# Sheet1.net
KiCad netlist of a schematic drawn in Altium Designer
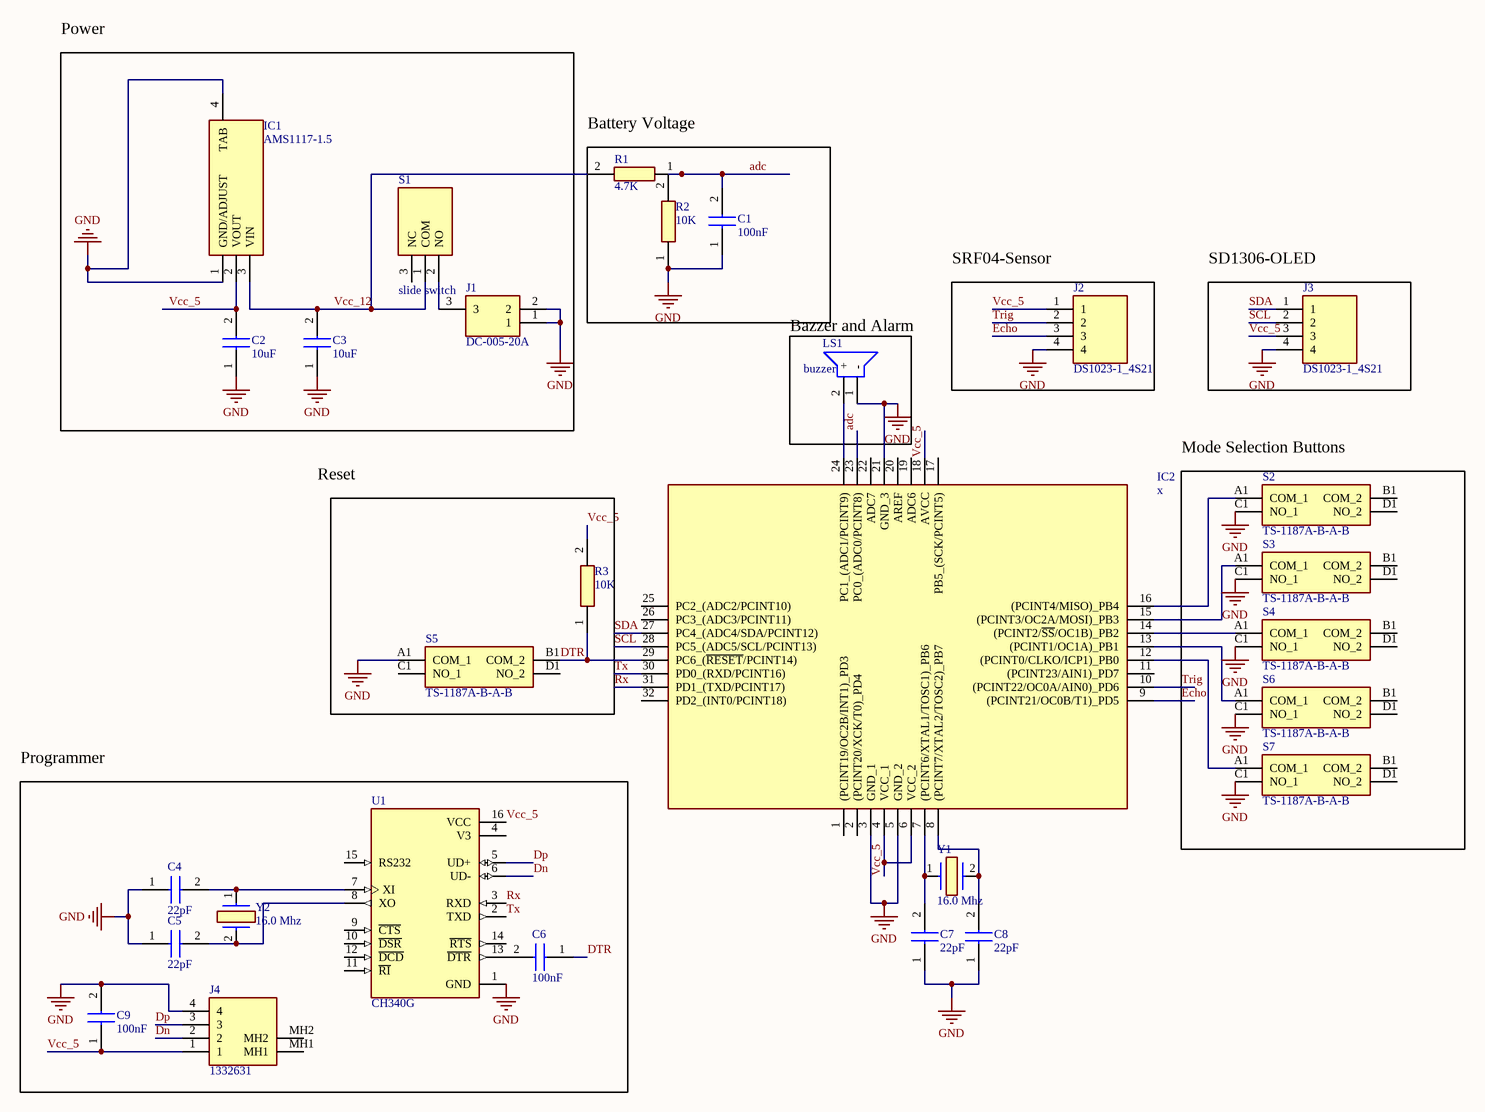
[diagram p0: Sheet1.SchDoc]

(export (version "E")
  (design (tool "Eeschema 10.0.6"))
  (components
    (comp (ref "C1")
      (value "100nF")
      (footprint "SamacSys:CAPC2012X130N")
      (description "Capacitor")
      (fields
        (field (name "MANUFACTURER_PART_NUMBER") "0805Y1000104KET")
        (field (name "MOUSER PART NUMBER") "843-0805Y1000104KET")
      )
      (libsource (lib "*") (part "0805Y1000104KET"))
    )
    (comp (ref "C2")
      (value "10uF")
      (footprint "SamacSys:CAPC2012X130N")
      (description "Capacitor")
      (fields
        (field (name "MANUFACTURER_PART_NUMBER") "0805Y1000104KET")
        (field (name "MOUSER PART NUMBER") "843-0805Y1000104KET")
      )
      (libsource (lib "*") (part "0805Y1000104KET"))
    )
    (comp (ref "C3")
      (value "10uF")
      (footprint "SamacSys:CAPC2012X130N")
      (description "Capacitor")
      (fields
        (field (name "MANUFACTURER_PART_NUMBER") "0805Y1000104KET")
        (field (name "MOUSER PART NUMBER") "843-0805Y1000104KET")
      )
      (libsource (lib "*") (part "0805Y1000104KET"))
    )
    (comp (ref "C4")
      (value "22pF")
      (footprint "SamacSys:CAPC2012X130N")
      (description "Capacitor")
      (fields (field (name "MANUFACTURER_PART_NUMBER") "0805J050 0223MXE01"))
      (libsource (lib "*") (part "0805J050_0223MXE01"))
    )
    (comp (ref "C5")
      (value "22pF")
      (footprint "SamacSys:CAPC2012X130N")
      (description "Capacitor")
      (fields (field (name "MANUFACTURER_PART_NUMBER") "0805J050 0223MXE01"))
      (libsource (lib "*") (part "0805J050_0223MXE01"))
    )
    (comp (ref "C6")
      (value "100nF")
      (footprint "SamacSys:CAPC2012X130N")
      (description "Capacitor")
      (fields (field (name "MANUFACTURER_PART_NUMBER") "0805J050 0223MXE01"))
      (libsource (lib "*") (part "0805J050_0223MXE01"))
    )
    (comp (ref "C7")
      (value "22pF")
      (footprint "SamacSys:CAPC2012X130N")
      (description "Capacitor")
      (fields (field (name "MANUFACTURER_PART_NUMBER") "0805J050 0223MXE01"))
      (libsource (lib "*") (part "0805J050_0223MXE01"))
    )
    (comp (ref "C8")
      (value "22pF")
      (footprint "SamacSys:CAPC2012X130N")
      (description "Capacitor")
      (fields (field (name "MANUFACTURER_PART_NUMBER") "0805J050 0223MXE01"))
      (libsource (lib "*") (part "0805J050_0223MXE01"))
    )
    (comp (ref "C9")
      (value "100nF")
      (footprint "SamacSys:CAPC2012X130N")
      (description "Capacitor")
      (fields (field (name "MANUFACTURER_PART_NUMBER") "0805J050 0223MXE01"))
      (libsource (lib "*") (part "0805J050_0223MXE01"))
    )
    (comp (ref "IC1")
      (value "AMS1117-1.5")
      (footprint "SamacSys:SOT229P700X180-4N")
      (description "Integrated Circuit")
      (libsource (lib "*") (part "AMS1117-1.5"))
    )
    (comp (ref "IC2")
      (value "x")
      (footprint "SamacSys:QFP80P900X900X120-32N")
      (description "Integrated Circuit")
      (fields
        (field (name "MANUFACTURER_PART_NUMBER") "ATMEGA328-AU")
        (field (name "MOUSER PART NUMBER") "556-ATMEGA328-AU")
      )
      (libsource (lib "*") (part "ATMEGA328-AU"))
    )
    (comp (ref "J1")
      (value "DC-005-20A")
      (footprint "SamacSys:DC00520A")
      (description "Connector")
      (libsource (lib "*") (part "DC-005-20A"))
    )
    (comp (ref "J2")
      (value "DS1023-1_4S21")
      (footprint "SamacSys:RHDR4W60P0X254_1X4_1016X250X840P")
      (description "Connector")
      (fields (field (name "MANUFACTURER_PART_NUMBER") "DS1023-1*4S21"))
      (libsource (lib "*") (part "DS1023-1_4S21"))
    )
    (comp (ref "J3")
      (value "DS1023-1_4S21")
      (footprint "SamacSys:RHDR4W60P0X254_1X4_1016X250X840P")
      (description "Connector")
      (fields (field (name "MANUFACTURER_PART_NUMBER") "DS1023-1*4S21"))
      (libsource (lib "*") (part "DS1023-1_4S21"))
    )
    (comp (ref "J4")
      (value "1332631")
      (footprint "SamacSys:1332631")
      (description "Connector")
      (libsource (lib "*") (part "1332631"))
    )
    (comp (ref "LS1")
      (value "buzzer")
      (footprint "SamacSys:CT1205SMTTR")
      (description "Loudspeaker or Buzzer")
      (fields
        (field (name "MANUFACTURER_PART_NUMBER") "CT-1205-SMT-TR")
        (field (name "MOUSER PART NUMBER") "490-CT-1205-SMT-TR")
      )
      (libsource (lib "*") (part "CT-1205-SMT-TR"))
    )
    (comp (ref "R1")
      (value "4.7K")
      (footprint "SamacSys:RESC2012X60N")
      (description "Resistor")
      (fields
        (field (name "MANUFACTURER_PART_NUMBER") "CRCW080510K0FKEAHP")
        (field (name "MOUSER PART NUMBER") "71-CRCW080510K0FKEAH")
      )
      (libsource (lib "") (part "CRCW080510K0FKEAHP_1"))
    )
    (comp (ref "R2")
      (value "10K")
      (footprint "SamacSys:RESC2012X60N")
      (description "Resistor")
      (fields
        (field (name "MANUFACTURER_PART_NUMBER") "CRCW080510K0FKEAHP")
        (field (name "MOUSER PART NUMBER") "71-CRCW080510K0FKEAH")
      )
      (libsource (lib "*") (part "CRCW080510K0FKEAHP"))
    )
    (comp (ref "R3")
      (value "10K")
      (footprint "SamacSys:RESC2012X60N")
      (description "Resistor")
      (fields
        (field (name "MANUFACTURER_PART_NUMBER") "CRCW080510K0FKEAHP")
        (field (name "MOUSER PART NUMBER") "71-CRCW080510K0FKEAH")
      )
      (libsource (lib "*") (part "CRCW080510K0FKEAHP"))
    )
    (comp (ref "S1")
      (value "slide switch")
      (footprint "SamacSys:090329001")
      (description "Switch")
      (fields
        (field (name "MANUFACTURER_PART_NUMBER") "09.03290.01")
        (field (name "MOUSER PART NUMBER") "123-09.03290.01")
      )
      (libsource (lib "*") (part "09.03290.01"))
    )
    (comp (ref "S2")
      (value "TS-1187A-B-A-B")
      (footprint "SamacSys:TS1187ABAB")
      (description "Switch")
      (libsource (lib "*") (part "TS-1187A-B-A-B"))
    )
    (comp (ref "S3")
      (value "TS-1187A-B-A-B")
      (footprint "SamacSys:TS1187ABAB")
      (description "Switch")
      (libsource (lib "*") (part "TS-1187A-B-A-B"))
    )
    (comp (ref "S4")
      (value "TS-1187A-B-A-B")
      (footprint "SamacSys:TS1187ABAB")
      (description "Switch")
      (libsource (lib "*") (part "TS-1187A-B-A-B"))
    )
    (comp (ref "S5")
      (value "TS-1187A-B-A-B")
      (footprint "SamacSys:TS1187ABAB")
      (description "Switch")
      (libsource (lib "*") (part "TS-1187A-B-A-B"))
    )
    (comp (ref "S6")
      (value "TS-1187A-B-A-B")
      (footprint "SamacSys:TS1187ABAB")
      (description "Switch")
      (libsource (lib "*") (part "TS-1187A-B-A-B"))
    )
    (comp (ref "S7")
      (value "TS-1187A-B-A-B")
      (footprint "SamacSys:TS1187ABAB")
      (description "Switch")
      (libsource (lib "*") (part "TS-1187A-B-A-B"))
    )
    (comp (ref "U1")
      (value "CH340G")
      (footprint "SOIC127P600X180-16N")
      (description "USB Interface Integrated Circuit")
      (fields (field (name "MP") "Ch340G") (field (name "MF") "WCH"))
      (libsource (lib "CH340G") (part "CH340G"))
    )
    (comp (ref "Y1")
      (value "16.0 Mhz")
      (footprint "SamacSys:16000MHz49USMX3050408518pFATF")
      (description "Crystal or Oscillator")
      (fields (field (name "MANUFACTURER_PART_NUMBER") "16.000MHz 49USMX/30/50/-40+85/18pF/ATF"))
      (libsource (lib "*") (part "16.000MHz_49USMX_30_50_-40+85_18pF_ATF"))
    )
    (comp (ref "Y2")
      (value "16.0 Mhz")
      (footprint "SamacSys:16000MHz49USMX3050408518pFATF")
      (description "Crystal or Oscillator")
      (fields (field (name "MANUFACTURER_PART_NUMBER") "16.000MHz 49USMX/30/50/-40+85/18pF/ATF"))
      (libsource (lib "") (part "16.000MHz_49USMX_30_50_-40+85_18pF_ATF_1"))
    )
  )
  (nets
    (net (code "1") (name "/DTR") (class "Default")
      (node (ref "C6") (pin "1") (pinfunction "1_1") (pintype "passive"))
      (node (ref "IC2") (pin "29") (pinfunction "PC6_(~{RESET}/PCINT14)_29") (pintype "passive"))
      (node (ref "R3") (pin "1") (pinfunction "1_1") (pintype "passive"))
      (node (ref "S5") (pin "B1") (pinfunction "COM_2_B1") (pintype "passive"))
    )
    (net (code "2") (name "/Dn") (class "Default")
      (node (ref "J4") (pin "2") (pinfunction "2_2") (pintype "passive"))
      (node (ref "U1") (pin "6") (pinfunction "UD-_6") (pintype "bidirectional"))
    )
    (net (code "3") (name "/Dp") (class "Default")
      (node (ref "J4") (pin "3") (pinfunction "3_3") (pintype "passive"))
      (node (ref "U1") (pin "5") (pinfunction "UD+_5") (pintype "bidirectional"))
    )
    (net (code "4") (name "/Echo") (class "Default")
      (node (ref "IC2") (pin "9") (pinfunction "(PCINT21/OC0B/T1)_PD5_9") (pintype "passive"))
      (node (ref "J2") (pin "3") (pinfunction "3_3") (pintype "passive"))
    )
    (net (code "5") (name "/Rx") (class "Default")
      (node (ref "IC2") (pin "31") (pinfunction "PD1_(TXD/PCINT17)_31") (pintype "passive"))
      (node (ref "U1") (pin "3") (pinfunction "RXD_3") (pintype "input"))
    )
    (net (code "6") (name "/SCL") (class "Default")
      (node (ref "IC2") (pin "28") (pinfunction "PC5_(ADC5/SCL/PCINT13)_28") (pintype "passive"))
      (node (ref "J3") (pin "2") (pinfunction "2_2") (pintype "passive"))
    )
    (net (code "7") (name "/SDA") (class "Default")
      (node (ref "IC2") (pin "27") (pinfunction "PC4_(ADC4/SDA/PCINT12)_27") (pintype "passive"))
      (node (ref "J3") (pin "1") (pinfunction "1_1") (pintype "passive"))
    )
    (net (code "8") (name "/Trig") (class "Default")
      (node (ref "IC2") (pin "10") (pinfunction "(PCINT22/OC0A/AIN0)_PD6_10") (pintype "passive"))
      (node (ref "J2") (pin "2") (pinfunction "2_2") (pintype "passive"))
    )
    (net (code "9") (name "/Tx") (class "Default")
      (node (ref "IC2") (pin "30") (pinfunction "PD0_(RXD/PCINT16)_30") (pintype "passive"))
      (node (ref "U1") (pin "2") (pinfunction "TXD_2") (pintype "output"))
    )
    (net (code "10") (name "/Vcc_5") (class "Default")
      (node (ref "C2") (pin "2") (pinfunction "2_2") (pintype "passive"))
      (node (ref "C9") (pin "1") (pinfunction "1_1") (pintype "passive"))
      (node (ref "IC1") (pin "2") (pinfunction "VOUT_2") (pintype "passive"))
      (node (ref "IC2") (pin "18") (pinfunction "AVCC_18") (pintype "passive"))
      (node (ref "IC2") (pin "4") (pinfunction "VCC_1_4") (pintype "passive"))
      (node (ref "IC2") (pin "6") (pinfunction "VCC_2_6") (pintype "passive"))
      (node (ref "J2") (pin "1") (pinfunction "1_1") (pintype "passive"))
      (node (ref "J3") (pin "3") (pinfunction "3_3") (pintype "passive"))
      (node (ref "J4") (pin "1") (pinfunction "1_1") (pintype "passive"))
      (node (ref "R3") (pin "2") (pinfunction "2_2") (pintype "passive"))
      (node (ref "U1") (pin "16") (pinfunction "VCC_16") (pintype "power_in"))
    )
    (net (code "11") (name "/Vcc_12") (class "Default")
      (node (ref "C3") (pin "2") (pinfunction "2_2") (pintype "passive"))
      (node (ref "IC1") (pin "3") (pinfunction "VIN_3") (pintype "passive"))
      (node (ref "R1") (pin "2") (pinfunction "2_2") (pintype "passive"))
      (node (ref "S1") (pin "1") (pinfunction "COM_1") (pintype "passive"))
    )
    (net (code "12") (name "/adc") (class "Default")
      (node (ref "C1") (pin "2") (pinfunction "2_2") (pintype "passive"))
      (node (ref "IC2") (pin "23") (pinfunction "PC0_(ADC0/PCINT8)_23") (pintype "passive"))
      (node (ref "R1") (pin "1") (pinfunction "1_1") (pintype "passive"))
      (node (ref "R2") (pin "2") (pinfunction "2_2") (pintype "passive"))
    )
    (net (code "13") (name "GND") (class "Default")
      (node (ref "C1") (pin "1") (pinfunction "1_1") (pintype "passive"))
      (node (ref "C2") (pin "1") (pinfunction "1_1") (pintype "passive"))
      (node (ref "C3") (pin "1") (pinfunction "1_1") (pintype "passive"))
      (node (ref "C4") (pin "1") (pinfunction "1_1") (pintype "passive"))
      (node (ref "C5") (pin "1") (pinfunction "1_1") (pintype "passive"))
      (node (ref "C7") (pin "1") (pinfunction "1_1") (pintype "passive"))
      (node (ref "C8") (pin "1") (pinfunction "1_1") (pintype "passive"))
      (node (ref "C9") (pin "2") (pinfunction "2_2") (pintype "passive"))
      (node (ref "IC1") (pin "1") (pinfunction "GND/ADJUST_1") (pintype "passive"))
      (node (ref "IC1") (pin "4") (pinfunction "TAB_4") (pintype "passive"))
      (node (ref "IC2") (pin "21") (pinfunction "GND_3_21") (pintype "passive"))
      (node (ref "IC2") (pin "3") (pinfunction "GND_1_3") (pintype "passive"))
      (node (ref "IC2") (pin "5") (pinfunction "GND_2_5") (pintype "passive"))
      (node (ref "J1") (pin "1") (pinfunction "1_1") (pintype "passive"))
      (node (ref "J1") (pin "2") (pinfunction "2_2") (pintype "passive"))
      (node (ref "J2") (pin "4") (pinfunction "4_4") (pintype "passive"))
      (node (ref "J3") (pin "4") (pinfunction "4_4") (pintype "passive"))
      (node (ref "J4") (pin "4") (pinfunction "4_4") (pintype "passive"))
      (node (ref "LS1") (pin "1") (pinfunction "-_1") (pintype "passive"))
      (node (ref "R2") (pin "1") (pinfunction "1_1") (pintype "passive"))
      (node (ref "S2") (pin "C1") (pinfunction "NO_1_C1") (pintype "passive"))
      (node (ref "S3") (pin "C1") (pinfunction "NO_1_C1") (pintype "passive"))
      (node (ref "S4") (pin "C1") (pinfunction "NO_1_C1") (pintype "passive"))
      (node (ref "S5") (pin "A1") (pinfunction "COM_1_A1") (pintype "passive"))
      (node (ref "S6") (pin "C1") (pinfunction "NO_1_C1") (pintype "passive"))
      (node (ref "S7") (pin "C1") (pinfunction "NO_1_C1") (pintype "passive"))
      (node (ref "U1") (pin "1") (pinfunction "GND_1") (pintype "power_in"))
    )
    (net (code "14") (name "Net-(IC2-(PCINT0{slash}CLKO{slash}ICP1)_PB0)") (class "Default")
      (node (ref "IC2") (pin "12") (pinfunction "(PCINT0/CLKO/ICP1)_PB0_12") (pintype "passive"))
      (node (ref "S7") (pin "A1") (pinfunction "COM_1_A1") (pintype "passive"))
    )
    (net (code "15") (name "Net-(IC2-(PCINT1{slash}OC1A)_PB1)") (class "Default")
      (node (ref "IC2") (pin "13") (pinfunction "(PCINT1/OC1A)_PB1_13") (pintype "passive"))
      (node (ref "S6") (pin "A1") (pinfunction "COM_1_A1") (pintype "passive"))
    )
    (net (code "16") (name "Net-(IC2-(PCINT2{slash}~{SS}{slash}OC1B)_PB2)") (class "Default")
      (node (ref "IC2") (pin "14") (pinfunction "(PCINT2/~{SS}/OC1B)_PB2_14") (pintype "passive"))
      (node (ref "S4") (pin "A1") (pinfunction "COM_1_A1") (pintype "passive"))
    )
    (net (code "17") (name "Net-(IC2-(PCINT3{slash}OC2A{slash}MOSI)_PB3)") (class "Default")
      (node (ref "IC2") (pin "15") (pinfunction "(PCINT3/OC2A/MOSI)_PB3_15") (pintype "passive"))
      (node (ref "S3") (pin "A1") (pinfunction "COM_1_A1") (pintype "passive"))
    )
    (net (code "18") (name "Net-(IC2-(PCINT4{slash}MISO)_PB4)") (class "Default")
      (node (ref "IC2") (pin "16") (pinfunction "(PCINT4/MISO)_PB4_16") (pintype "passive"))
      (node (ref "S2") (pin "A1") (pinfunction "COM_1_A1") (pintype "passive"))
    )
    (net (code "19") (name "Net-(IC2-(PCINT6{slash}XTAL1{slash}TOSC1)_PB6)") (class "Default")
      (node (ref "C7") (pin "2") (pinfunction "2_2") (pintype "passive"))
      (node (ref "IC2") (pin "7") (pinfunction "(PCINT6/XTAL1/TOSC1)_PB6_7") (pintype "passive"))
      (node (ref "Y1") (pin "1") (pinfunction "1_1") (pintype "passive"))
    )
    (net (code "20") (name "Net-(IC2-(PCINT7{slash}XTAL2{slash}TOSC2)_PB7)") (class "Default")
      (node (ref "C8") (pin "2") (pinfunction "2_2") (pintype "passive"))
      (node (ref "IC2") (pin "8") (pinfunction "(PCINT7/XTAL2/TOSC2)_PB7_8") (pintype "passive"))
      (node (ref "Y1") (pin "2") (pinfunction "2_2") (pintype "passive"))
    )
    (net (code "21") (name "Net-(IC2-PC1_(ADC1{slash}PCINT9))") (class "Default")
      (node (ref "IC2") (pin "24") (pinfunction "PC1_(ADC1/PCINT9)_24") (pintype "passive"))
      (node (ref "LS1") (pin "2") (pinfunction "+_2") (pintype "passive"))
    )
    (net (code "22") (name "Net-(S1-NO)") (class "Default")
      (node (ref "J1") (pin "3") (pinfunction "3_3") (pintype "passive"))
      (node (ref "S1") (pin "2") (pinfunction "NO_2") (pintype "passive"))
    )
    (net (code "23") (name "Net-(U1-XI)") (class "Default")
      (node (ref "C4") (pin "2") (pinfunction "2_2") (pintype "passive"))
      (node (ref "U1") (pin "7") (pinfunction "XI_7") (pintype "input"))
      (node (ref "Y2") (pin "1") (pinfunction "1_1") (pintype "passive"))
    )
    (net (code "24") (name "Net-(U1-XO)") (class "Default")
      (node (ref "C5") (pin "2") (pinfunction "2_2") (pintype "passive"))
      (node (ref "U1") (pin "8") (pinfunction "XO_8") (pintype "output"))
      (node (ref "Y2") (pin "2") (pinfunction "2_2") (pintype "passive"))
    )
    (net (code "25") (name "Net-(U1-~{DTR})") (class "Default")
      (node (ref "C6") (pin "2") (pinfunction "2_2") (pintype "passive"))
      (node (ref "U1") (pin "13") (pinfunction "~{DTR}_13") (pintype "output"))
    )
    (net (code "26") (name "unconnected-(IC2-(PCINT19{slash}OC2B{slash}INT1)_PD3-Pad1)") (class "Default")
      (node (ref "IC2") (pin "1") (pinfunction "(PCINT19/OC2B/INT1)_PD3_1") (pintype "passive"))
    )
    (net (code "27") (name "unconnected-(IC2-(PCINT20{slash}XCK{slash}T0)_PD4-Pad2)") (class "Default")
      (node (ref "IC2") (pin "2") (pinfunction "(PCINT20/XCK/T0)_PD4_2") (pintype "passive"))
    )
    (net (code "28") (name "unconnected-(IC2-(PCINT23{slash}AIN1)_PD7-Pad11)") (class "Default")
      (node (ref "IC2") (pin "11") (pinfunction "(PCINT23/AIN1)_PD7_11") (pintype "passive"))
    )
    (net (code "29") (name "unconnected-(IC2-ADC6-Pad19)") (class "Default")
      (node (ref "IC2") (pin "19") (pinfunction "ADC6_19") (pintype "passive"))
    )
    (net (code "30") (name "unconnected-(IC2-ADC7-Pad22)") (class "Default")
      (node (ref "IC2") (pin "22") (pinfunction "ADC7_22") (pintype "passive"))
    )
    (net (code "31") (name "unconnected-(IC2-AREF-Pad20)") (class "Default")
      (node (ref "IC2") (pin "20") (pinfunction "AREF_20") (pintype "passive"))
    )
    (net (code "32") (name "unconnected-(IC2-PB5_(SCK{slash}PCINT5)-Pad17)") (class "Default")
      (node (ref "IC2") (pin "17") (pinfunction "PB5_(SCK/PCINT5)_17") (pintype "passive"))
    )
    (net (code "33") (name "unconnected-(IC2-PC2_(ADC2{slash}PCINT10)-Pad25)") (class "Default")
      (node (ref "IC2") (pin "25") (pinfunction "PC2_(ADC2/PCINT10)_25") (pintype "passive"))
    )
    (net (code "34") (name "unconnected-(IC2-PC3_(ADC3{slash}PCINT11)-Pad26)") (class "Default")
      (node (ref "IC2") (pin "26") (pinfunction "PC3_(ADC3/PCINT11)_26") (pintype "passive"))
    )
    (net (code "35") (name "unconnected-(IC2-PD2_(INT0{slash}PCINT18)-Pad32)") (class "Default")
      (node (ref "IC2") (pin "32") (pinfunction "PD2_(INT0/PCINT18)_32") (pintype "passive"))
    )
    (net (code "36") (name "unconnected-(J4-PadMH1)") (class "Default")
      (node (ref "J4") (pin "MH1") (pinfunction "MH1_MH1") (pintype "passive"))
    )
    (net (code "37") (name "unconnected-(J4-PadMH2)") (class "Default")
      (node (ref "J4") (pin "MH2") (pinfunction "MH2_MH2") (pintype "passive"))
    )
    (net (code "38") (name "unconnected-(S1-NC-Pad3)") (class "Default")
      (node (ref "S1") (pin "3") (pinfunction "NC_3") (pintype "passive"))
    )
    (net (code "39") (name "unconnected-(S2-COM_2-PadB1)") (class "Default")
      (node (ref "S2") (pin "B1") (pinfunction "COM_2_B1") (pintype "passive"))
    )
    (net (code "40") (name "unconnected-(S2-NO_2-PadD1)") (class "Default")
      (node (ref "S2") (pin "D1") (pinfunction "NO_2_D1") (pintype "passive"))
    )
    (net (code "41") (name "unconnected-(S3-COM_2-PadB1)") (class "Default")
      (node (ref "S3") (pin "B1") (pinfunction "COM_2_B1") (pintype "passive"))
    )
    (net (code "42") (name "unconnected-(S3-NO_2-PadD1)") (class "Default")
      (node (ref "S3") (pin "D1") (pinfunction "NO_2_D1") (pintype "passive"))
    )
    (net (code "43") (name "unconnected-(S4-COM_2-PadB1)") (class "Default")
      (node (ref "S4") (pin "B1") (pinfunction "COM_2_B1") (pintype "passive"))
    )
    (net (code "44") (name "unconnected-(S4-NO_2-PadD1)") (class "Default")
      (node (ref "S4") (pin "D1") (pinfunction "NO_2_D1") (pintype "passive"))
    )
    (net (code "45") (name "unconnected-(S5-NO_1-PadC1)") (class "Default")
      (node (ref "S5") (pin "C1") (pinfunction "NO_1_C1") (pintype "passive"))
    )
    (net (code "46") (name "unconnected-(S5-NO_2-PadD1)") (class "Default")
      (node (ref "S5") (pin "D1") (pinfunction "NO_2_D1") (pintype "passive"))
    )
    (net (code "47") (name "unconnected-(S6-COM_2-PadB1)") (class "Default")
      (node (ref "S6") (pin "B1") (pinfunction "COM_2_B1") (pintype "passive"))
    )
    (net (code "48") (name "unconnected-(S6-NO_2-PadD1)") (class "Default")
      (node (ref "S6") (pin "D1") (pinfunction "NO_2_D1") (pintype "passive"))
    )
    (net (code "49") (name "unconnected-(S7-COM_2-PadB1)") (class "Default")
      (node (ref "S7") (pin "B1") (pinfunction "COM_2_B1") (pintype "passive"))
    )
    (net (code "50") (name "unconnected-(S7-NO_2-PadD1)") (class "Default")
      (node (ref "S7") (pin "D1") (pinfunction "NO_2_D1") (pintype "passive"))
    )
    (net (code "51") (name "unconnected-(U1-RS232-Pad15)") (class "Default")
      (node (ref "U1") (pin "15") (pinfunction "RS232_15") (pintype "input"))
    )
    (net (code "52") (name "unconnected-(U1-V3-Pad4)") (class "Default")
      (node (ref "U1") (pin "4") (pinfunction "V3_4") (pintype "power_in"))
    )
    (net (code "53") (name "unconnected-(U1-~{CTS}-Pad9)") (class "Default")
      (node (ref "U1") (pin "9") (pinfunction "~{CTS}_9") (pintype "input"))
    )
    (net (code "54") (name "unconnected-(U1-~{DCD}-Pad12)") (class "Default")
      (node (ref "U1") (pin "12") (pinfunction "~{DCD}_12") (pintype "input"))
    )
    (net (code "55") (name "unconnected-(U1-~{DSR}-Pad10)") (class "Default")
      (node (ref "U1") (pin "10") (pinfunction "~{DSR}_10") (pintype "input"))
    )
    (net (code "56") (name "unconnected-(U1-~{RI}-Pad11)") (class "Default")
      (node (ref "U1") (pin "11") (pinfunction "~{RI}_11") (pintype "input"))
    )
    (net (code "57") (name "unconnected-(U1-~{RTS}-Pad14)") (class "Default")
      (node (ref "U1") (pin "14") (pinfunction "~{RTS}_14") (pintype "output"))
    )
  )
)
